# SSRBoard.net
KiCad netlist of a schematic drawn in EAGLE
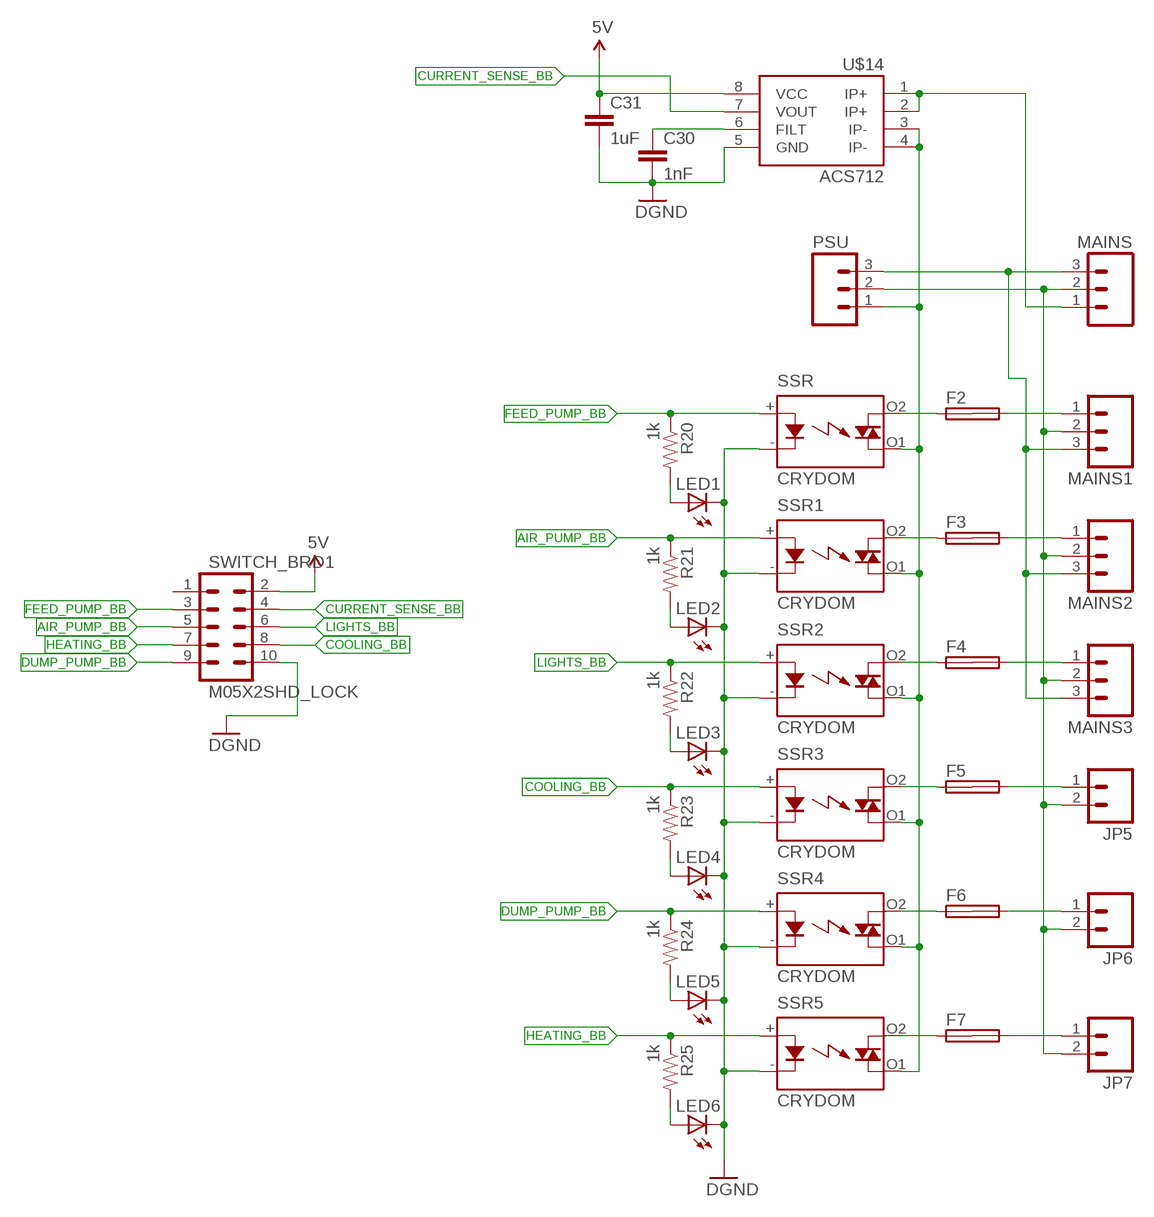
[diagram p0: schematic, sheet 1]

(export (version "E")
  (design (tool "Eeschema 10.0.6"))
  (components
    (comp (ref "C30")
      (value "1nF")
      (footprint "eagle-import:0805")
      (libsource (lib "eagle-import") (part "CAP0805"))
    )
    (comp (ref "C31")
      (value "1uF")
      (footprint "eagle-import:0805")
      (libsource (lib "eagle-import") (part "CAP0805"))
    )
    (comp (ref "F2")
      (value "SHK20L")
      (footprint "eagle-import:SHK20L")
      (fields (field (name "OC_FARNELL") "unknown") (field (name "OC_NEWARK") "unknown"))
      (libsource (lib "eagle-import") (part "SHK20L"))
    )
    (comp (ref "F3")
      (value "SHK20L")
      (footprint "eagle-import:SHK20L")
      (libsource (lib "eagle-import") (part "SHK20L"))
    )
    (comp (ref "F4")
      (value "SHK20L")
      (footprint "eagle-import:SHK20L")
      (fields (field (name "OC_FARNELL") "unknown") (field (name "OC_NEWARK") "unknown"))
      (libsource (lib "eagle-import") (part "SHK20L"))
    )
    (comp (ref "F5")
      (value "SHK20L")
      (footprint "eagle-import:SHK20L")
      (fields (field (name "OC_FARNELL") "unknown") (field (name "OC_NEWARK") "unknown"))
      (libsource (lib "eagle-import") (part "SHK20L"))
    )
    (comp (ref "F6")
      (value "SHK20L")
      (footprint "eagle-import:SHK20L")
      (fields (field (name "OC_FARNELL") "unknown") (field (name "OC_NEWARK") "unknown"))
      (libsource (lib "eagle-import") (part "SHK20L"))
    )
    (comp (ref "F7")
      (value "SHK20L")
      (footprint "eagle-import:SHK20L")
      (fields (field (name "OC_FARNELL") "unknown") (field (name "OC_NEWARK") "unknown"))
      (libsource (lib "eagle-import") (part "SHK20L"))
    )
    (comp (ref "JP5")
      (value "M025MM")
      (footprint "eagle-import:SCREWTERMINAL-5MM-2")
      (libsource (lib "eagle-import") (part "M025MM"))
    )
    (comp (ref "JP6")
      (value "M025MM")
      (footprint "eagle-import:SCREWTERMINAL-5MM-2")
      (libsource (lib "eagle-import") (part "M025MM"))
    )
    (comp (ref "JP7")
      (value "M025MM")
      (footprint "eagle-import:SCREWTERMINAL-5MM-2")
      (libsource (lib "eagle-import") (part "M025MM"))
    )
    (comp (ref "LED1")
      (value "LEDSML0805")
      (footprint "eagle-import:SML0805")
      (libsource (lib "eagle-import") (part "LEDSML0805"))
    )
    (comp (ref "LED2")
      (value "LEDSML0805")
      (footprint "eagle-import:SML0805")
      (libsource (lib "eagle-import") (part "LEDSML0805"))
    )
    (comp (ref "LED3")
      (value "LEDSML0805")
      (footprint "eagle-import:SML0805")
      (libsource (lib "eagle-import") (part "LEDSML0805"))
    )
    (comp (ref "LED4")
      (value "LEDSML0805")
      (footprint "eagle-import:SML0805")
      (libsource (lib "eagle-import") (part "LEDSML0805"))
    )
    (comp (ref "LED5")
      (value "LEDSML0805")
      (footprint "eagle-import:SML0805")
      (libsource (lib "eagle-import") (part "LEDSML0805"))
    )
    (comp (ref "LED6")
      (value "LEDSML0805")
      (footprint "eagle-import:SML0805")
      (libsource (lib "eagle-import") (part "LEDSML0805"))
    )
    (comp (ref "MAINS")
      (value "M03-SCREW-5MM")
      (footprint "eagle-import:SCREWTERMINAL-5MM-3")
      (libsource (lib "eagle-import") (part "M03-SCREW-5MM"))
    )
    (comp (ref "MAINS1")
      (value "M03-SCREW-5MM")
      (footprint "eagle-import:SCREWTERMINAL-5MM-3")
      (libsource (lib "eagle-import") (part "M03-SCREW-5MM"))
    )
    (comp (ref "MAINS2")
      (value "M03-SCREW-5MM")
      (footprint "eagle-import:SCREWTERMINAL-5MM-3")
      (libsource (lib "eagle-import") (part "M03-SCREW-5MM"))
    )
    (comp (ref "MAINS3")
      (value "M03-SCREW-5MM")
      (footprint "eagle-import:SCREWTERMINAL-5MM-3")
      (libsource (lib "eagle-import") (part "M03-SCREW-5MM"))
    )
    (comp (ref "PSU")
      (value "M03-SCREW-5MM")
      (footprint "eagle-import:SCREWTERMINAL-5MM-3")
      (libsource (lib "eagle-import") (part "M03-SCREW-5MM"))
    )
    (comp (ref "R20")
      (value "1k")
      (footprint "eagle-import:0805")
      (libsource (lib "eagle-import") (part "RESISTOR0805-RES"))
    )
    (comp (ref "R21")
      (value "1k")
      (footprint "eagle-import:0805")
      (libsource (lib "eagle-import") (part "RESISTOR0805-RES"))
    )
    (comp (ref "R22")
      (value "1k")
      (footprint "eagle-import:0805")
      (libsource (lib "eagle-import") (part "RESISTOR0805-RES"))
    )
    (comp (ref "R23")
      (value "1k")
      (footprint "eagle-import:0805")
      (libsource (lib "eagle-import") (part "RESISTOR0805-RES"))
    )
    (comp (ref "R24")
      (value "1k")
      (footprint "eagle-import:0805")
      (libsource (lib "eagle-import") (part "RESISTOR0805-RES"))
    )
    (comp (ref "R25")
      (value "1k")
      (footprint "eagle-import:0805")
      (libsource (lib "eagle-import") (part "RESISTOR0805-RES"))
    )
    (comp (ref "SSR")
      (value "CRYDOM")
      (footprint "eagle-import:AQG")
      (fields (field (name "MPN") "AQG22224"))
      (libsource (lib "eagle-import") (part "AQG22224"))
    )
    (comp (ref "SSR1")
      (value "CRYDOM")
      (footprint "eagle-import:AQG")
      (fields
        (field (name "MPN") "AQG22224")
        (field (name "MPN_1") "AQG22224")
        (field (name "OC_FARNELL") "unknown")
        (field (name "OC_NEWARK") "11N2589")
      )
      (libsource (lib "eagle-import") (part "AQG22224"))
    )
    (comp (ref "SSR2")
      (value "CRYDOM")
      (footprint "eagle-import:AQG")
      (fields
        (field (name "MPN") "AQG22224")
        (field (name "MPN_1") "AQG22224")
        (field (name "OC_FARNELL") "unknown")
        (field (name "OC_NEWARK") "11N2589")
      )
      (libsource (lib "eagle-import") (part "AQG22224"))
    )
    (comp (ref "SSR3")
      (value "CRYDOM")
      (footprint "eagle-import:AQG")
      (fields
        (field (name "MPN") "AQG22224")
        (field (name "MPN_1") "AQG22224")
        (field (name "OC_FARNELL") "unknown")
        (field (name "OC_NEWARK") "11N2589")
      )
      (libsource (lib "eagle-import") (part "AQG22224"))
    )
    (comp (ref "SSR4")
      (value "CRYDOM")
      (footprint "eagle-import:AQG")
      (fields
        (field (name "MPN") "AQG22224")
        (field (name "MPN_1") "AQG22224")
        (field (name "OC_FARNELL") "unknown")
        (field (name "OC_NEWARK") "11N2589")
      )
      (libsource (lib "eagle-import") (part "AQG22224"))
    )
    (comp (ref "SSR5")
      (value "CRYDOM")
      (footprint "eagle-import:AQG")
      (fields
        (field (name "MPN") "AQG22224")
        (field (name "MPN_1") "AQG22224")
        (field (name "OC_FARNELL") "unknown")
        (field (name "OC_NEWARK") "11N2589")
      )
      (libsource (lib "eagle-import") (part "AQG22224"))
    )
    (comp (ref "SWITCH_BRD1")
      (value "M05X2SHD_LOCK")
      (footprint "eagle-import:2X5-SHROUDED_LOCK")
      (libsource (lib "eagle-import") (part "M05X2SHD_LOCK"))
    )
    (comp (ref "U$14")
      (value "ACS712")
      (footprint "eagle-import:SO08")
      (libsource (lib "eagle-import") (part "ACS712"))
    )
  )
  (nets
    (net (code "1") (name "5V") (class "Default")
      (node (ref "C31") (pin "1") (pinfunction "1_1") (pintype "passive"))
      (node (ref "SWITCH_BRD1") (pin "2") (pinfunction "2_2") (pintype "passive"))
      (node (ref "U$14") (pin "8") (pinfunction "VCC_8") (pintype "bidirectional"))
    )
    (net (code "2") (name "AIR_PUMP_BB") (class "Default")
      (node (ref "R21") (pin "1") (pinfunction "1_1") (pintype "passive"))
      (node (ref "SSR1") (pin "+") (pinfunction "A_+") (pintype "passive"))
      (node (ref "SWITCH_BRD1") (pin "5") (pinfunction "5_5") (pintype "passive"))
    )
    (net (code "3") (name "COOLING_BB") (class "Default")
      (node (ref "R23") (pin "1") (pinfunction "1_1") (pintype "passive"))
      (node (ref "SSR3") (pin "+") (pinfunction "A_+") (pintype "passive"))
      (node (ref "SWITCH_BRD1") (pin "8") (pinfunction "8_8") (pintype "passive"))
    )
    (net (code "4") (name "CURRENT_SENSE_BB") (class "Default")
      (node (ref "SWITCH_BRD1") (pin "4") (pinfunction "4_4") (pintype "passive"))
      (node (ref "U$14") (pin "7") (pinfunction "VOUT_7") (pintype "bidirectional"))
    )
    (net (code "5") (name "DGND") (class "Default")
      (node (ref "C30") (pin "2") (pinfunction "2_2") (pintype "passive"))
      (node (ref "C31") (pin "2") (pinfunction "2_2") (pintype "passive"))
      (node (ref "LED1") (pin "C") (pinfunction "C_C") (pintype "passive"))
      (node (ref "LED2") (pin "C") (pinfunction "C_C") (pintype "passive"))
      (node (ref "LED3") (pin "C") (pinfunction "C_C") (pintype "passive"))
      (node (ref "LED4") (pin "C") (pinfunction "C_C") (pintype "passive"))
      (node (ref "LED5") (pin "C") (pinfunction "C_C") (pintype "passive"))
      (node (ref "LED6") (pin "C") (pinfunction "C_C") (pintype "passive"))
      (node (ref "SSR") (pin "-") (pinfunction "K_-") (pintype "passive"))
      (node (ref "SSR1") (pin "-") (pinfunction "K_-") (pintype "passive"))
      (node (ref "SSR2") (pin "-") (pinfunction "K_-") (pintype "passive"))
      (node (ref "SSR3") (pin "-") (pinfunction "K_-") (pintype "passive"))
      (node (ref "SSR4") (pin "-") (pinfunction "K_-") (pintype "passive"))
      (node (ref "SSR5") (pin "-") (pinfunction "K_-") (pintype "passive"))
      (node (ref "SWITCH_BRD1") (pin "10") (pinfunction "10_10") (pintype "passive"))
      (node (ref "U$14") (pin "5") (pinfunction "GND_5") (pintype "bidirectional"))
    )
    (net (code "6") (name "DUMP_PUMP_BB") (class "Default")
      (node (ref "R24") (pin "1") (pinfunction "1_1") (pintype "passive"))
      (node (ref "SSR4") (pin "+") (pinfunction "A_+") (pintype "passive"))
      (node (ref "SWITCH_BRD1") (pin "9") (pinfunction "9_9") (pintype "passive"))
    )
    (net (code "7") (name "FEED_PUMP_BB") (class "Default")
      (node (ref "R20") (pin "1") (pinfunction "1_1") (pintype "passive"))
      (node (ref "SSR") (pin "+") (pinfunction "A_+") (pintype "passive"))
      (node (ref "SWITCH_BRD1") (pin "3") (pinfunction "3_3") (pintype "passive"))
    )
    (net (code "8") (name "HEATING_BB") (class "Default")
      (node (ref "R25") (pin "1") (pinfunction "1_1") (pintype "passive"))
      (node (ref "SSR5") (pin "+") (pinfunction "A_+") (pintype "passive"))
      (node (ref "SWITCH_BRD1") (pin "7") (pinfunction "7_7") (pintype "passive"))
    )
    (net (code "9") (name "LIGHTS_BB") (class "Default")
      (node (ref "R22") (pin "1") (pinfunction "1_1") (pintype "passive"))
      (node (ref "SSR2") (pin "+") (pinfunction "A_+") (pintype "passive"))
      (node (ref "SWITCH_BRD1") (pin "6") (pinfunction "6_6") (pintype "passive"))
    )
    (net (code "10") (name "Net-(F2-Pad2A)") (class "Default")
      (node (ref "F2") (pin "2A") (pinfunction "2A_2A") (pintype "passive"))
      (node (ref "MAINS1") (pin "1") (pinfunction "1_1") (pintype "passive"))
    )
    (net (code "11") (name "Net-(F3-Pad2A)") (class "Default")
      (node (ref "F3") (pin "2A") (pinfunction "2A_2A") (pintype "passive"))
      (node (ref "MAINS2") (pin "1") (pinfunction "1_1") (pintype "passive"))
    )
    (net (code "12") (name "Net-(F4-Pad2A)") (class "Default")
      (node (ref "F4") (pin "2A") (pinfunction "2A_2A") (pintype "passive"))
      (node (ref "MAINS3") (pin "1") (pinfunction "1_1") (pintype "passive"))
    )
    (net (code "13") (name "Net-(F5-Pad2A)") (class "Default")
      (node (ref "F5") (pin "2A") (pinfunction "2A_2A") (pintype "passive"))
      (node (ref "JP5") (pin "1") (pinfunction "1_1") (pintype "passive"))
    )
    (net (code "14") (name "Net-(F6-Pad2A)") (class "Default")
      (node (ref "F6") (pin "2A") (pinfunction "2A_2A") (pintype "passive"))
      (node (ref "JP6") (pin "1") (pinfunction "1_1") (pintype "passive"))
    )
    (net (code "15") (name "Net-(F7-Pad2A)") (class "Default")
      (node (ref "F7") (pin "2A") (pinfunction "2A_2A") (pintype "passive"))
      (node (ref "JP7") (pin "1") (pinfunction "1_1") (pintype "passive"))
    )
    (net (code "16") (name "Net-(JP5-Pad2)") (class "Default")
      (node (ref "JP5") (pin "2") (pinfunction "2_2") (pintype "passive"))
      (node (ref "JP6") (pin "2") (pinfunction "2_2") (pintype "passive"))
      (node (ref "JP7") (pin "2") (pinfunction "2_2") (pintype "passive"))
      (node (ref "MAINS") (pin "2") (pinfunction "2_2") (pintype "passive"))
      (node (ref "MAINS1") (pin "2") (pinfunction "2_2") (pintype "passive"))
      (node (ref "MAINS2") (pin "2") (pinfunction "2_2") (pintype "passive"))
      (node (ref "MAINS3") (pin "2") (pinfunction "2_2") (pintype "passive"))
      (node (ref "PSU") (pin "2") (pinfunction "2_2") (pintype "passive"))
    )
    (net (code "17") (name "Net-(LED1-PadA)") (class "Default")
      (node (ref "LED1") (pin "A") (pinfunction "A_A") (pintype "passive"))
      (node (ref "R20") (pin "2") (pinfunction "2_2") (pintype "passive"))
    )
    (net (code "18") (name "Net-(LED2-PadA)") (class "Default")
      (node (ref "LED2") (pin "A") (pinfunction "A_A") (pintype "passive"))
      (node (ref "R21") (pin "2") (pinfunction "2_2") (pintype "passive"))
    )
    (net (code "19") (name "Net-(LED3-PadA)") (class "Default")
      (node (ref "LED3") (pin "A") (pinfunction "A_A") (pintype "passive"))
      (node (ref "R22") (pin "2") (pinfunction "2_2") (pintype "passive"))
    )
    (net (code "20") (name "Net-(LED4-PadA)") (class "Default")
      (node (ref "LED4") (pin "A") (pinfunction "A_A") (pintype "passive"))
      (node (ref "R23") (pin "2") (pinfunction "2_2") (pintype "passive"))
    )
    (net (code "21") (name "Net-(LED5-PadA)") (class "Default")
      (node (ref "LED5") (pin "A") (pinfunction "A_A") (pintype "passive"))
      (node (ref "R24") (pin "2") (pinfunction "2_2") (pintype "passive"))
    )
    (net (code "22") (name "Net-(LED6-PadA)") (class "Default")
      (node (ref "LED6") (pin "A") (pinfunction "A_A") (pintype "passive"))
      (node (ref "R25") (pin "2") (pinfunction "2_2") (pintype "passive"))
    )
    (net (code "23") (name "Net-(MAINS-Pad1)") (class "Default")
      (node (ref "MAINS") (pin "1") (pinfunction "1_1") (pintype "passive"))
      (node (ref "U$14") (pin "1") (pinfunction "IP+_1") (pintype "bidirectional"))
      (node (ref "U$14") (pin "2") (pinfunction "IP+_2") (pintype "bidirectional"))
    )
    (net (code "24") (name "Net-(MAINS-Pad3)") (class "Default")
      (node (ref "MAINS") (pin "3") (pinfunction "3_3") (pintype "passive"))
      (node (ref "MAINS1") (pin "3") (pinfunction "3_3") (pintype "passive"))
      (node (ref "MAINS2") (pin "3") (pinfunction "3_3") (pintype "passive"))
      (node (ref "MAINS3") (pin "3") (pinfunction "3_3") (pintype "passive"))
      (node (ref "PSU") (pin "3") (pinfunction "3_3") (pintype "passive"))
    )
    (net (code "25") (name "Net-(SSR-DS1)") (class "Default")
      (node (ref "F2") (pin "1A") (pinfunction "1A_1A") (pintype "passive"))
      (node (ref "SSR") (pin "O2") (pinfunction "DS1_O2") (pintype "passive"))
    )
    (net (code "26") (name "Net-(SSR-DS2)") (class "Default")
      (node (ref "PSU") (pin "1") (pinfunction "1_1") (pintype "passive"))
      (node (ref "SSR") (pin "O1") (pinfunction "DS2_O1") (pintype "passive"))
      (node (ref "SSR1") (pin "O1") (pinfunction "DS2_O1") (pintype "passive"))
      (node (ref "SSR2") (pin "O1") (pinfunction "DS2_O1") (pintype "passive"))
      (node (ref "SSR3") (pin "O1") (pinfunction "DS2_O1") (pintype "passive"))
      (node (ref "SSR4") (pin "O1") (pinfunction "DS2_O1") (pintype "passive"))
      (node (ref "SSR5") (pin "O1") (pinfunction "DS2_O1") (pintype "passive"))
      (node (ref "U$14") (pin "3") (pinfunction "IP-_3") (pintype "bidirectional"))
      (node (ref "U$14") (pin "4") (pinfunction "IP-_4") (pintype "bidirectional"))
    )
    (net (code "27") (name "Net-(SSR1-DS1)") (class "Default")
      (node (ref "F3") (pin "1A") (pinfunction "1A_1A") (pintype "passive"))
      (node (ref "SSR1") (pin "O2") (pinfunction "DS1_O2") (pintype "passive"))
    )
    (net (code "28") (name "Net-(SSR2-DS1)") (class "Default")
      (node (ref "F4") (pin "1A") (pinfunction "1A_1A") (pintype "passive"))
      (node (ref "SSR2") (pin "O2") (pinfunction "DS1_O2") (pintype "passive"))
    )
    (net (code "29") (name "Net-(SSR3-DS1)") (class "Default")
      (node (ref "F5") (pin "1A") (pinfunction "1A_1A") (pintype "passive"))
      (node (ref "SSR3") (pin "O2") (pinfunction "DS1_O2") (pintype "passive"))
    )
    (net (code "30") (name "Net-(SSR4-DS1)") (class "Default")
      (node (ref "F6") (pin "1A") (pinfunction "1A_1A") (pintype "passive"))
      (node (ref "SSR4") (pin "O2") (pinfunction "DS1_O2") (pintype "passive"))
    )
    (net (code "31") (name "Net-(SSR5-DS1)") (class "Default")
      (node (ref "F7") (pin "1A") (pinfunction "1A_1A") (pintype "passive"))
      (node (ref "SSR5") (pin "O2") (pinfunction "DS1_O2") (pintype "passive"))
    )
    (net (code "32") (name "Net-(U$14-FILT)") (class "Default")
      (node (ref "C30") (pin "1") (pinfunction "1_1") (pintype "passive"))
      (node (ref "U$14") (pin "6") (pinfunction "FILT_6") (pintype "bidirectional"))
    )
    (net (code "33") (name "unconnected-(F2-Pad1B)") (class "Default")
      (node (ref "F2") (pin "1B") (pinfunction "1B_1B") (pintype "passive"))
    )
    (net (code "34") (name "unconnected-(F2-Pad2B)") (class "Default")
      (node (ref "F2") (pin "2B") (pinfunction "2B_2B") (pintype "passive"))
    )
    (net (code "35") (name "unconnected-(F3-Pad1B)") (class "Default")
      (node (ref "F3") (pin "1B") (pinfunction "1B_1B") (pintype "passive"))
    )
    (net (code "36") (name "unconnected-(F3-Pad2B)") (class "Default")
      (node (ref "F3") (pin "2B") (pinfunction "2B_2B") (pintype "passive"))
    )
    (net (code "37") (name "unconnected-(F4-Pad1B)") (class "Default")
      (node (ref "F4") (pin "1B") (pinfunction "1B_1B") (pintype "passive"))
    )
    (net (code "38") (name "unconnected-(F4-Pad2B)") (class "Default")
      (node (ref "F4") (pin "2B") (pinfunction "2B_2B") (pintype "passive"))
    )
    (net (code "39") (name "unconnected-(F5-Pad1B)") (class "Default")
      (node (ref "F5") (pin "1B") (pinfunction "1B_1B") (pintype "passive"))
    )
    (net (code "40") (name "unconnected-(F5-Pad2B)") (class "Default")
      (node (ref "F5") (pin "2B") (pinfunction "2B_2B") (pintype "passive"))
    )
    (net (code "41") (name "unconnected-(F6-Pad1B)") (class "Default")
      (node (ref "F6") (pin "1B") (pinfunction "1B_1B") (pintype "passive"))
    )
    (net (code "42") (name "unconnected-(F6-Pad2B)") (class "Default")
      (node (ref "F6") (pin "2B") (pinfunction "2B_2B") (pintype "passive"))
    )
    (net (code "43") (name "unconnected-(F7-Pad1B)") (class "Default")
      (node (ref "F7") (pin "1B") (pinfunction "1B_1B") (pintype "passive"))
    )
    (net (code "44") (name "unconnected-(F7-Pad2B)") (class "Default")
      (node (ref "F7") (pin "2B") (pinfunction "2B_2B") (pintype "passive"))
    )
    (net (code "45") (name "unconnected-(SWITCH_BRD1-Pad1)") (class "Default")
      (node (ref "SWITCH_BRD1") (pin "1") (pinfunction "1_1") (pintype "passive"))
    )
  )
)
